# GBCartSchematics.net
KiCad netlist of a schematic drawn in EAGLE
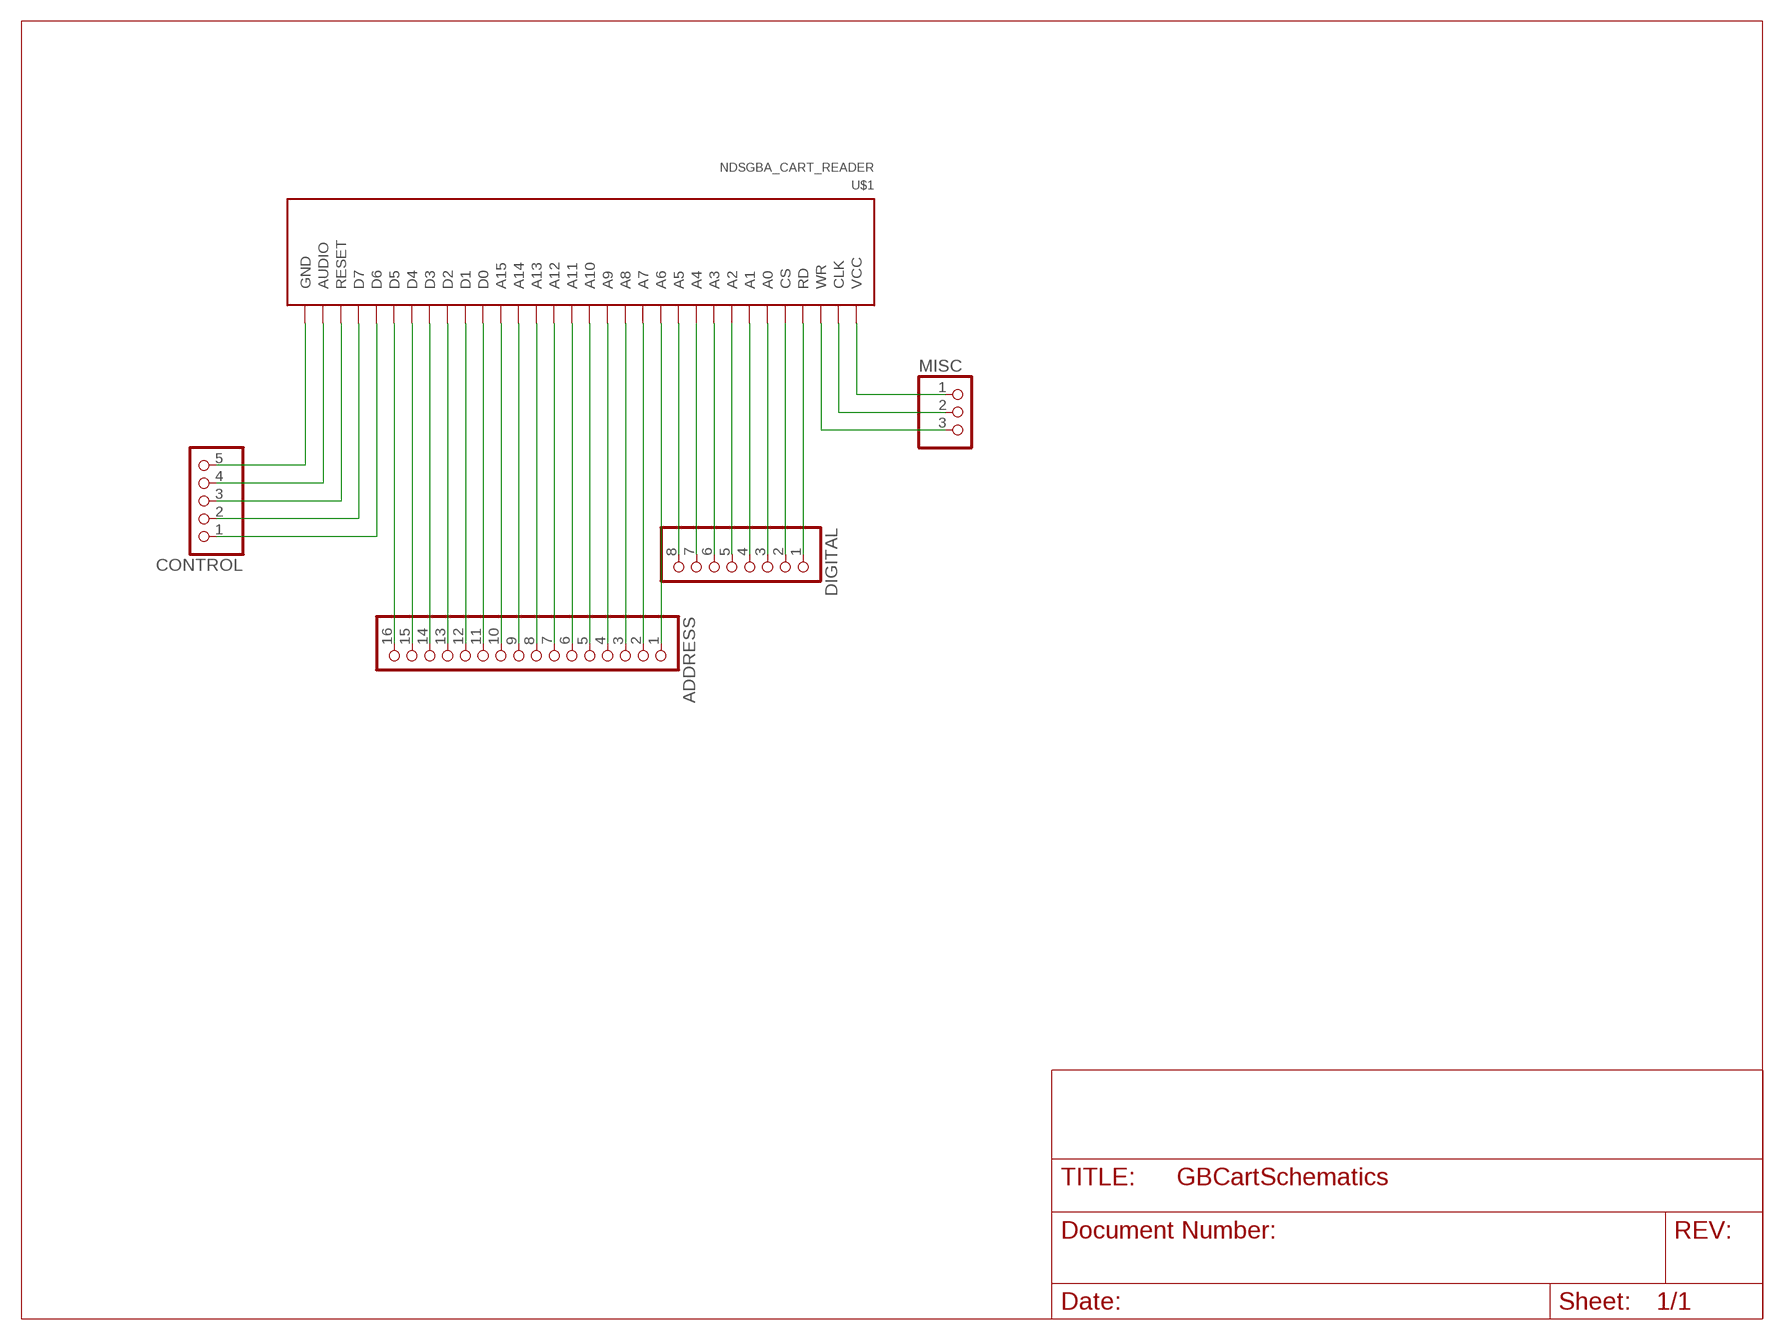
[diagram p0: schematic, sheet 1]

(export (version "E")
  (design (tool "Eeschema 10.0.6"))
  (components
    (comp (ref "ADDRESS")
      (value "PINHD-1X16")
      (footprint "eagle-import:1X16")
      (libsource (lib "eagle-import") (part "PINHD-1X16"))
    )
    (comp (ref "CONTROL")
      (value "PINHD-1X5")
      (footprint "eagle-import:1X05")
      (libsource (lib "eagle-import") (part "PINHD-1X5"))
    )
    (comp (ref "DIGITAL")
      (value "PINHD-1X8")
      (footprint "eagle-import:1X08")
      (libsource (lib "eagle-import") (part "PINHD-1X8"))
    )
    (comp (ref "MISC")
      (value "PINHD-1X3")
      (footprint "eagle-import:1X03")
      (libsource (lib "eagle-import") (part "PINHD-1X3"))
    )
    (comp (ref "U$1")
      (value "NDSGBA_CART_READER")
      (footprint "eagle-import:NDSGBA_CART_READER")
      (libsource (lib "eagle-import") (part "NDSGBA_CART_READER"))
    )
  )
  (nets
    (net (code "1") (name "Net-(U$1-A0)") (class "Default")
      (node (ref "DIGITAL") (pin "3") (pinfunction "3_3") (pintype "passive"))
      (node (ref "U$1") (pin "6") (pinfunction "A0_6") (pintype "bidirectional"))
    )
    (net (code "2") (name "Net-(U$1-A1)") (class "Default")
      (node (ref "DIGITAL") (pin "4") (pinfunction "4_4") (pintype "passive"))
      (node (ref "U$1") (pin "7") (pinfunction "A1_7") (pintype "bidirectional"))
    )
    (net (code "3") (name "Net-(U$1-A2)") (class "Default")
      (node (ref "DIGITAL") (pin "5") (pinfunction "5_5") (pintype "passive"))
      (node (ref "U$1") (pin "8") (pinfunction "A2_8") (pintype "bidirectional"))
    )
    (net (code "4") (name "Net-(U$1-A3)") (class "Default")
      (node (ref "DIGITAL") (pin "6") (pinfunction "6_6") (pintype "passive"))
      (node (ref "U$1") (pin "9") (pinfunction "A3_9") (pintype "bidirectional"))
    )
    (net (code "5") (name "Net-(U$1-A4)") (class "Default")
      (node (ref "DIGITAL") (pin "7") (pinfunction "7_7") (pintype "passive"))
      (node (ref "U$1") (pin "10") (pinfunction "A4_10") (pintype "bidirectional"))
    )
    (net (code "6") (name "Net-(U$1-A5)") (class "Default")
      (node (ref "DIGITAL") (pin "8") (pinfunction "8_8") (pintype "passive"))
      (node (ref "U$1") (pin "11") (pinfunction "A5_11") (pintype "bidirectional"))
    )
    (net (code "7") (name "Net-(U$1-A6)") (class "Default")
      (node (ref "ADDRESS") (pin "1") (pinfunction "1_1") (pintype "passive"))
      (node (ref "U$1") (pin "12") (pinfunction "A6_12") (pintype "bidirectional"))
    )
    (net (code "8") (name "Net-(U$1-A7)") (class "Default")
      (node (ref "ADDRESS") (pin "2") (pinfunction "2_2") (pintype "passive"))
      (node (ref "U$1") (pin "13") (pinfunction "A7_13") (pintype "bidirectional"))
    )
    (net (code "9") (name "Net-(U$1-A8)") (class "Default")
      (node (ref "ADDRESS") (pin "3") (pinfunction "3_3") (pintype "passive"))
      (node (ref "U$1") (pin "14") (pinfunction "A8_14") (pintype "bidirectional"))
    )
    (net (code "10") (name "Net-(U$1-A9)") (class "Default")
      (node (ref "ADDRESS") (pin "4") (pinfunction "4_4") (pintype "passive"))
      (node (ref "U$1") (pin "15") (pinfunction "A9_15") (pintype "bidirectional"))
    )
    (net (code "11") (name "Net-(U$1-A10)") (class "Default")
      (node (ref "ADDRESS") (pin "5") (pinfunction "5_5") (pintype "passive"))
      (node (ref "U$1") (pin "16") (pinfunction "A10_16") (pintype "bidirectional"))
    )
    (net (code "12") (name "Net-(U$1-A11)") (class "Default")
      (node (ref "ADDRESS") (pin "6") (pinfunction "6_6") (pintype "passive"))
      (node (ref "U$1") (pin "17") (pinfunction "A11_17") (pintype "bidirectional"))
    )
    (net (code "13") (name "Net-(U$1-A12)") (class "Default")
      (node (ref "ADDRESS") (pin "7") (pinfunction "7_7") (pintype "passive"))
      (node (ref "U$1") (pin "18") (pinfunction "A12_18") (pintype "bidirectional"))
    )
    (net (code "14") (name "Net-(U$1-A13)") (class "Default")
      (node (ref "ADDRESS") (pin "8") (pinfunction "8_8") (pintype "passive"))
      (node (ref "U$1") (pin "19") (pinfunction "A13_19") (pintype "bidirectional"))
    )
    (net (code "15") (name "Net-(U$1-A14)") (class "Default")
      (node (ref "ADDRESS") (pin "9") (pinfunction "9_9") (pintype "passive"))
      (node (ref "U$1") (pin "20") (pinfunction "A14_20") (pintype "bidirectional"))
    )
    (net (code "16") (name "Net-(U$1-A15)") (class "Default")
      (node (ref "ADDRESS") (pin "10") (pinfunction "10_10") (pintype "passive"))
      (node (ref "U$1") (pin "21") (pinfunction "A15_21") (pintype "bidirectional"))
    )
    (net (code "17") (name "Net-(U$1-AUDIO)") (class "Default")
      (node (ref "CONTROL") (pin "4") (pinfunction "4_4") (pintype "passive"))
      (node (ref "U$1") (pin "31") (pinfunction "AUDIO_31") (pintype "bidirectional"))
    )
    (net (code "18") (name "Net-(U$1-CLK)") (class "Default")
      (node (ref "MISC") (pin "2") (pinfunction "2_2") (pintype "passive"))
      (node (ref "U$1") (pin "2") (pinfunction "CLK_2") (pintype "bidirectional"))
    )
    (net (code "19") (name "Net-(U$1-CS)") (class "Default")
      (node (ref "DIGITAL") (pin "2") (pinfunction "2_2") (pintype "passive"))
      (node (ref "U$1") (pin "5") (pinfunction "CS_5") (pintype "bidirectional"))
    )
    (net (code "20") (name "Net-(U$1-D0)") (class "Default")
      (node (ref "ADDRESS") (pin "11") (pinfunction "11_11") (pintype "passive"))
      (node (ref "U$1") (pin "22") (pinfunction "D0_22") (pintype "bidirectional"))
    )
    (net (code "21") (name "Net-(U$1-D1)") (class "Default")
      (node (ref "ADDRESS") (pin "12") (pinfunction "12_12") (pintype "passive"))
      (node (ref "U$1") (pin "23") (pinfunction "D1_23") (pintype "bidirectional"))
    )
    (net (code "22") (name "Net-(U$1-D2)") (class "Default")
      (node (ref "ADDRESS") (pin "13") (pinfunction "13_13") (pintype "passive"))
      (node (ref "U$1") (pin "24") (pinfunction "D2_24") (pintype "bidirectional"))
    )
    (net (code "23") (name "Net-(U$1-D3)") (class "Default")
      (node (ref "ADDRESS") (pin "14") (pinfunction "14_14") (pintype "passive"))
      (node (ref "U$1") (pin "25") (pinfunction "D3_25") (pintype "bidirectional"))
    )
    (net (code "24") (name "Net-(U$1-D4)") (class "Default")
      (node (ref "ADDRESS") (pin "15") (pinfunction "15_15") (pintype "passive"))
      (node (ref "U$1") (pin "26") (pinfunction "D4_26") (pintype "bidirectional"))
    )
    (net (code "25") (name "Net-(U$1-D5)") (class "Default")
      (node (ref "ADDRESS") (pin "16") (pinfunction "16_16") (pintype "passive"))
      (node (ref "U$1") (pin "27") (pinfunction "D5_27") (pintype "bidirectional"))
    )
    (net (code "26") (name "Net-(U$1-D6)") (class "Default")
      (node (ref "CONTROL") (pin "1") (pinfunction "1_1") (pintype "passive"))
      (node (ref "U$1") (pin "28") (pinfunction "D6_28") (pintype "bidirectional"))
    )
    (net (code "27") (name "Net-(U$1-D7)") (class "Default")
      (node (ref "CONTROL") (pin "2") (pinfunction "2_2") (pintype "passive"))
      (node (ref "U$1") (pin "29") (pinfunction "D7_29") (pintype "bidirectional"))
    )
    (net (code "28") (name "Net-(U$1-GND)") (class "Default")
      (node (ref "CONTROL") (pin "5") (pinfunction "5_5") (pintype "passive"))
      (node (ref "U$1") (pin "32") (pinfunction "GND_32") (pintype "power_in"))
    )
    (net (code "29") (name "Net-(U$1-RD)") (class "Default")
      (node (ref "DIGITAL") (pin "1") (pinfunction "1_1") (pintype "passive"))
      (node (ref "U$1") (pin "4") (pinfunction "RD_4") (pintype "bidirectional"))
    )
    (net (code "30") (name "Net-(U$1-RESET)") (class "Default")
      (node (ref "CONTROL") (pin "3") (pinfunction "3_3") (pintype "passive"))
      (node (ref "U$1") (pin "30") (pinfunction "RESET_30") (pintype "bidirectional"))
    )
    (net (code "31") (name "Net-(U$1-VCC)") (class "Default")
      (node (ref "MISC") (pin "1") (pinfunction "1_1") (pintype "passive"))
      (node (ref "U$1") (pin "1") (pinfunction "VCC_1") (pintype "power_in"))
    )
    (net (code "32") (name "Net-(U$1-WR)") (class "Default")
      (node (ref "MISC") (pin "3") (pinfunction "3_3") (pintype "passive"))
      (node (ref "U$1") (pin "3") (pinfunction "WR_3") (pintype "bidirectional"))
    )
  )
)
